# schematic2Diodes.net
KiCad netlist of a schematic drawn in EAGLE
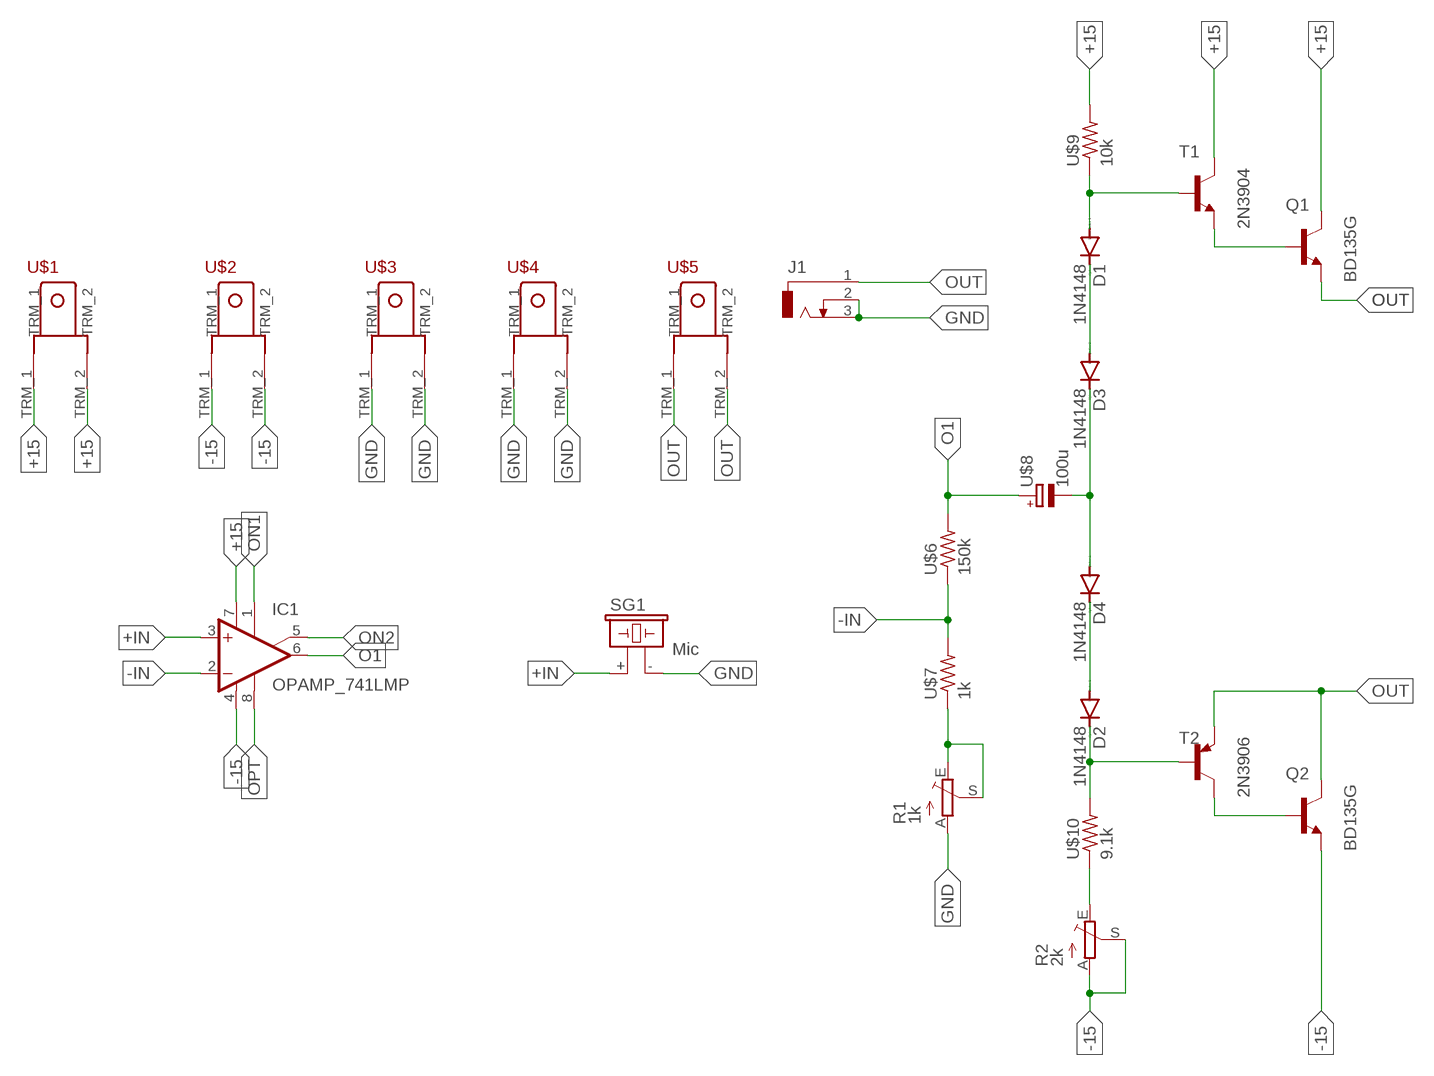
[diagram p0: schematic, sheet 1]

(export (version "E")
  (design (tool "Eeschema 10.0.6"))
  (components
    (comp (ref "D1")
      (value "1N4148")
      (footprint "eagle-import:DO35-10")
      (libsource (lib "eagle-import") (part "1N4148DO35-10"))
    )
    (comp (ref "D2")
      (value "1N4148")
      (footprint "eagle-import:DO35-10")
      (libsource (lib "eagle-import") (part "1N4148DO35-10"))
    )
    (comp (ref "D3")
      (value "1N4148")
      (footprint "eagle-import:DO35-10")
      (libsource (lib "eagle-import") (part "1N4148DO35-10"))
    )
    (comp (ref "D4")
      (value "1N4148")
      (footprint "eagle-import:DO35-10")
      (libsource (lib "eagle-import") (part "1N4148DO35-10"))
    )
    (comp (ref "IC1")
      (value "OPAMP_741LMP")
      (footprint "eagle-import:DIL08")
      (libsource (lib "eagle-import") (part "OPAMP_741PLM"))
    )
    (comp (ref "J1")
      (value "CON_JACK")
      (footprint "eagle-import:DCJ0303")
      (libsource (lib "eagle-import") (part "CON_JACK"))
    )
    (comp (ref "Q1")
      (value "BD135G")
      (footprint "eagle-import:TO229P780X300X2000-3")
      (fields (field (name "MF") "ON Semiconductor"))
      (libsource (lib "eagle-import") (part "BD135G"))
    )
    (comp (ref "Q2")
      (value "BD135G")
      (footprint "eagle-import:TO229P780X300X2000-3")
      (fields (field (name "MF") "ON Semiconductor"))
      (libsource (lib "eagle-import") (part "BD135G"))
    )
    (comp (ref "R1")
      (value "1k")
      (footprint "eagle-import:CA6V")
      (libsource (lib "eagle-import") (part "TRIM_EU-CA6V"))
    )
    (comp (ref "R2")
      (value "2k")
      (footprint "eagle-import:CA6V")
      (libsource (lib "eagle-import") (part "TRIM_EU-CA6V"))
    )
    (comp (ref "SG1")
      (value "Mic")
      (footprint "eagle-import:F_CM12P")
      (libsource (lib "eagle-import") (part "BUZZER"))
    )
    (comp (ref "T1")
      (value "2N3904")
      (footprint "eagle-import:TO92-EBC")
      (libsource (lib "eagle-import") (part "-NPN-TO92-EBC2N3904"))
    )
    (comp (ref "T2")
      (value "2N3906")
      (footprint "eagle-import:TO92-EBC")
      (libsource (lib "eagle-import") (part "-PNP-TO92-EBC2N3906"))
    )
    (comp (ref "U$1")
      (value "TERMINAL_EDITED")
      (footprint "eagle-import:TERMINAL_EDITED")
      (libsource (lib "eagle-import") (part "TERMINAL_EDITED"))
    )
    (comp (ref "U$2")
      (value "TERMINAL_EDITED")
      (footprint "eagle-import:TERMINAL_EDITED")
      (libsource (lib "eagle-import") (part "TERMINAL_EDITED"))
    )
    (comp (ref "U$3")
      (value "TERMINAL_EDITED")
      (footprint "eagle-import:TERMINAL_EDITED")
      (libsource (lib "eagle-import") (part "TERMINAL_EDITED"))
    )
    (comp (ref "U$4")
      (value "TERMINAL_EDITED")
      (footprint "eagle-import:TERMINAL_EDITED")
      (libsource (lib "eagle-import") (part "TERMINAL_EDITED"))
    )
    (comp (ref "U$5")
      (value "TERMINAL_EDITED")
      (footprint "eagle-import:TERMINAL_EDITED")
      (libsource (lib "eagle-import") (part "TERMINAL_EDITED"))
    )
    (comp (ref "U$6")
      (value "150k")
      (footprint "eagle-import:0204_7")
      (libsource (lib "eagle-import") (part "RES-7"))
    )
    (comp (ref "U$7")
      (value "1k")
      (footprint "eagle-import:0204_7")
      (libsource (lib "eagle-import") (part "RES-7"))
    )
    (comp (ref "U$8")
      (value "100u")
      (footprint "eagle-import:E3,5-8")
      (libsource (lib "eagle-import") (part "CAP_POL"))
    )
    (comp (ref "U$9")
      (value "10k")
      (footprint "eagle-import:0204_7")
      (libsource (lib "eagle-import") (part "RES-7"))
    )
    (comp (ref "U$10")
      (value "9.1k")
      (footprint "eagle-import:0204_7")
      (libsource (lib "eagle-import") (part "RES-7"))
    )
  )
  (nets
    (net (code "1") (name "+15") (class "Default")
      (node (ref "IC1") (pin "7") (pinfunction "V+_7") (pintype "power_in"))
      (node (ref "Q1") (pin "2") (pinfunction "C_2") (pintype "passive"))
      (node (ref "T1") (pin "C") (pinfunction "C_C") (pintype "passive"))
      (node (ref "U$1") (pin "TRM_1") (pinfunction "TRM_1_TRM_1") (pintype "bidirectional"))
      (node (ref "U$1") (pin "TRM_2") (pinfunction "TRM_2_TRM_2") (pintype "bidirectional"))
      (node (ref "U$9") (pin "2") (pinfunction "2_2") (pintype "passive"))
    )
    (net (code "2") (name "+IN") (class "Default")
      (node (ref "IC1") (pin "3") (pinfunction "+IN_3") (pintype "input"))
      (node (ref "SG1") (pin "+") (pinfunction "1_+") (pintype "passive"))
    )
    (net (code "3") (name "-15") (class "Default")
      (node (ref "IC1") (pin "4") (pinfunction "V-_4") (pintype "power_in"))
      (node (ref "Q2") (pin "1") (pinfunction "E_1") (pintype "passive"))
      (node (ref "R2") (pin "A") (pinfunction "A_A") (pintype "passive"))
      (node (ref "R2") (pin "S") (pinfunction "S_S") (pintype "passive"))
      (node (ref "U$2") (pin "TRM_1") (pinfunction "TRM_1_TRM_1") (pintype "bidirectional"))
      (node (ref "U$2") (pin "TRM_2") (pinfunction "TRM_2_TRM_2") (pintype "bidirectional"))
    )
    (net (code "4") (name "-IN") (class "Default")
      (node (ref "IC1") (pin "2") (pinfunction "-IN_2") (pintype "input"))
      (node (ref "U$6") (pin "1") (pinfunction "1_1") (pintype "passive"))
      (node (ref "U$7") (pin "2") (pinfunction "2_2") (pintype "passive"))
    )
    (net (code "5") (name "GND") (class "Default")
      (node (ref "J1") (pin "2") (pinfunction "2_2") (pintype "passive"))
      (node (ref "J1") (pin "3") (pinfunction "3_3") (pintype "passive"))
      (node (ref "R1") (pin "A") (pinfunction "A_A") (pintype "passive"))
      (node (ref "SG1") (pin "-") (pinfunction "2_-") (pintype "passive"))
      (node (ref "U$3") (pin "TRM_1") (pinfunction "TRM_1_TRM_1") (pintype "bidirectional"))
      (node (ref "U$3") (pin "TRM_2") (pinfunction "TRM_2_TRM_2") (pintype "bidirectional"))
      (node (ref "U$4") (pin "TRM_1") (pinfunction "TRM_1_TRM_1") (pintype "bidirectional"))
      (node (ref "U$4") (pin "TRM_2") (pinfunction "TRM_2_TRM_2") (pintype "bidirectional"))
    )
    (net (code "6") (name "Net-(D1-PadA)") (class "Default")
      (node (ref "D1") (pin "A") (pinfunction "A_A") (pintype "passive"))
      (node (ref "T1") (pin "B") (pinfunction "B_B") (pintype "passive"))
      (node (ref "U$9") (pin "1") (pinfunction "1_1") (pintype "passive"))
    )
    (net (code "7") (name "Net-(D1-PadC)") (class "Default")
      (node (ref "D1") (pin "C") (pinfunction "C_C") (pintype "passive"))
      (node (ref "D3") (pin "A") (pinfunction "A_A") (pintype "passive"))
    )
    (net (code "8") (name "Net-(D2-PadA)") (class "Default")
      (node (ref "D2") (pin "A") (pinfunction "A_A") (pintype "passive"))
      (node (ref "D4") (pin "C") (pinfunction "C_C") (pintype "passive"))
    )
    (net (code "9") (name "Net-(D2-PadC)") (class "Default")
      (node (ref "D2") (pin "C") (pinfunction "C_C") (pintype "passive"))
      (node (ref "T2") (pin "B") (pinfunction "B_B") (pintype "passive"))
      (node (ref "U$10") (pin "2") (pinfunction "2_2") (pintype "passive"))
    )
    (net (code "10") (name "Net-(D3-PadC)") (class "Default")
      (node (ref "D3") (pin "C") (pinfunction "C_C") (pintype "passive"))
      (node (ref "D4") (pin "A") (pinfunction "A_A") (pintype "passive"))
      (node (ref "U$8") (pin "-") (pinfunction "-_-") (pintype "passive"))
    )
    (net (code "11") (name "Net-(Q1-B)") (class "Default")
      (node (ref "Q1") (pin "3") (pinfunction "B_3") (pintype "passive"))
      (node (ref "T1") (pin "E") (pinfunction "E_E") (pintype "passive"))
    )
    (net (code "12") (name "Net-(Q2-B)") (class "Default")
      (node (ref "Q2") (pin "3") (pinfunction "B_3") (pintype "passive"))
      (node (ref "T2") (pin "C") (pinfunction "C_C") (pintype "passive"))
    )
    (net (code "13") (name "Net-(R1-PadE)") (class "Default")
      (node (ref "R1") (pin "E") (pinfunction "E_E") (pintype "passive"))
      (node (ref "R1") (pin "S") (pinfunction "S_S") (pintype "passive"))
      (node (ref "U$7") (pin "1") (pinfunction "1_1") (pintype "passive"))
    )
    (net (code "14") (name "Net-(R2-PadE)") (class "Default")
      (node (ref "R2") (pin "E") (pinfunction "E_E") (pintype "passive"))
      (node (ref "U$10") (pin "1") (pinfunction "1_1") (pintype "passive"))
    )
    (net (code "15") (name "O1") (class "Default")
      (node (ref "IC1") (pin "6") (pinfunction "OUT_6") (pintype "output"))
      (node (ref "U$6") (pin "2") (pinfunction "2_2") (pintype "passive"))
      (node (ref "U$8") (pin "+") (pinfunction "+_+") (pintype "passive"))
    )
    (net (code "16") (name "ON1") (class "Default")
      (node (ref "IC1") (pin "1") (pinfunction "ON1_1") (pintype "passive"))
    )
    (net (code "17") (name "ON2") (class "Default")
      (node (ref "IC1") (pin "5") (pinfunction "ON2_5") (pintype "passive"))
    )
    (net (code "18") (name "OPT") (class "Default")
      (node (ref "IC1") (pin "8") (pinfunction "OPT_8") (pintype "passive"))
    )
    (net (code "19") (name "OUT") (class "Default")
      (node (ref "J1") (pin "1") (pinfunction "1_1") (pintype "passive"))
      (node (ref "Q1") (pin "1") (pinfunction "E_1") (pintype "passive"))
      (node (ref "Q2") (pin "2") (pinfunction "C_2") (pintype "passive"))
      (node (ref "T2") (pin "E") (pinfunction "E_E") (pintype "passive"))
      (node (ref "U$5") (pin "TRM_1") (pinfunction "TRM_1_TRM_1") (pintype "bidirectional"))
      (node (ref "U$5") (pin "TRM_2") (pinfunction "TRM_2_TRM_2") (pintype "bidirectional"))
    )
  )
)
